# Power.net
KiCad netlist of a schematic drawn in Altium Designer
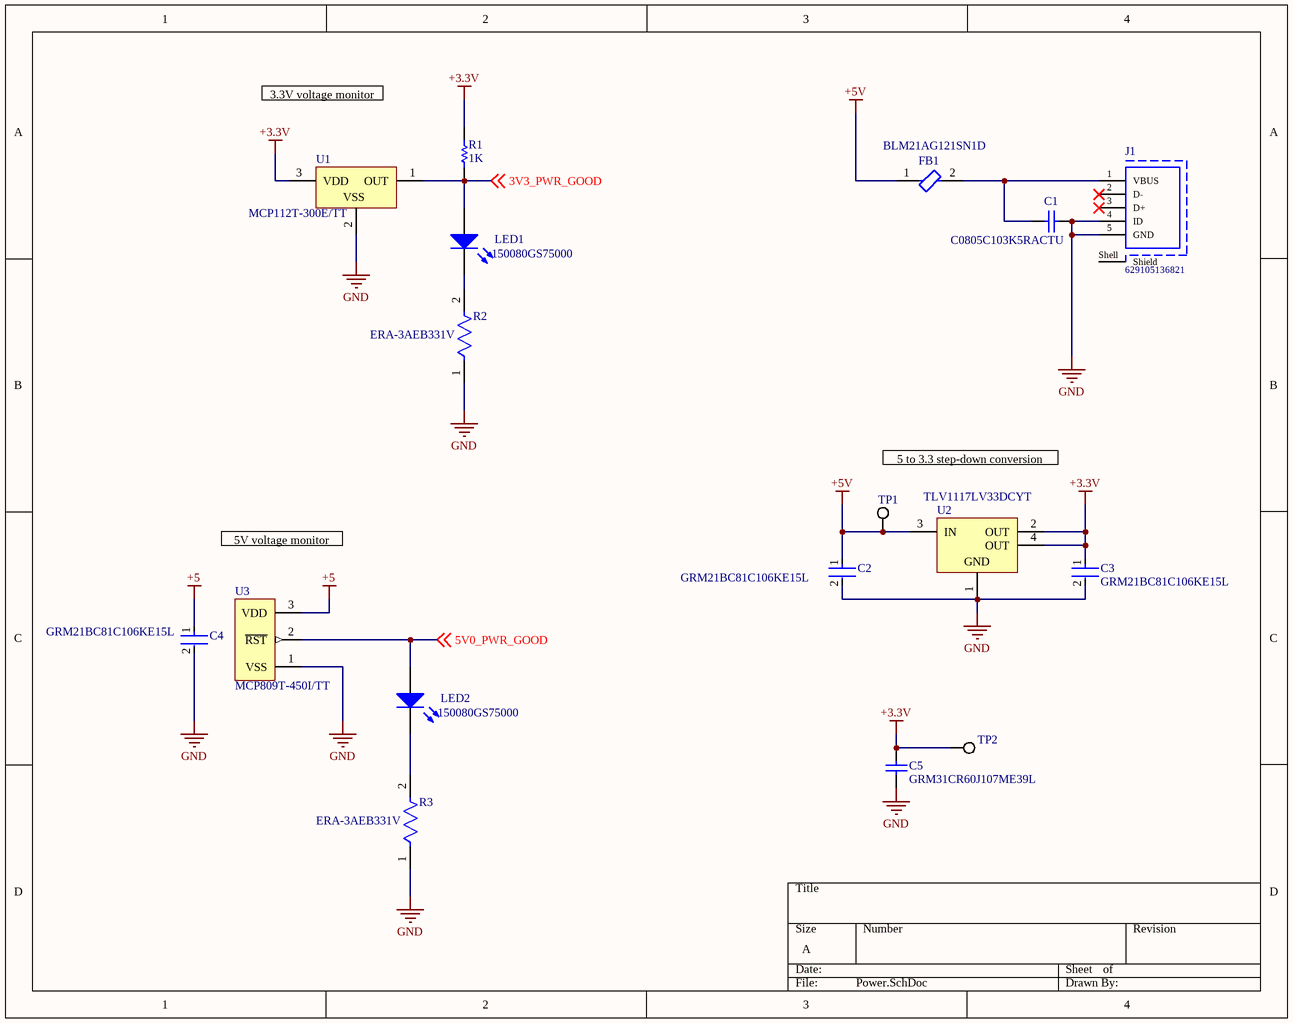
[diagram p0: Power.SchDoc]

(export (version "E")
  (design (tool "Eeschema 10.0.6"))
  (components
    (comp (ref "C1")
      (value "C0805C103K5RACTU")
      (footprint "CAPC2013X88X50LL20T25")
      (fields (field (name "MANUFACTURER") "Kemet"))
      (libsource (lib "Altium Content Vault") (part "CAP"))
    )
    (comp (ref "C2")
      (value "GRM21BC81C106KE15L")
      (footprint "FP-GRM21B-0_1-IPC_B")
      (description "Chip Multilayer Ceramic Capacitors for General Purpose, 0805, 10uF, X6S, 22%, 10%, 16V")
      (fields (field (name "VOLTAGE") "16V") (field (name "TOLERANCE") "10%"))
      (libsource (lib "Altium Content Vault") (part "b4654b650e69147ec39a6b967a45e02"))
    )
    (comp (ref "C3")
      (value "GRM21BC81C106KE15L")
      (footprint "FP-GRM21B-0_1-IPC_B")
      (description "Chip Multilayer Ceramic Capacitors for General Purpose, 0805, 10uF, X6S, 22%, 10%, 16V")
      (fields (field (name "VOLTAGE") "16V") (field (name "TOLERANCE") "10%"))
      (libsource (lib "Altium Content Vault") (part "b4654b650e69147ec39a6b967a45e02"))
    )
    (comp (ref "C4")
      (value "GRM21BC81C106KE15L")
      (footprint "FP-GRM21B-0_1-IPC_B")
      (description "Chip Multilayer Ceramic Capacitors for General Purpose, 0805, 10uF, X6S, 22%, 10%, 16V")
      (fields (field (name "VOLTAGE") "16V") (field (name "TOLERANCE") "10%"))
      (libsource (lib "Altium Content Vault") (part "b4654b650e69147ec39a6b967a45e02"))
    )
    (comp (ref "C5")
      (value "GRM31CR60J107ME39L")
      (footprint "CAPC3216X190X55ML30T25")
      (description "Chip Capacitor, 100 uF, +/- 20%, 6.3 V, -55 to 85 degC, 1206 (3216 Metric), RoHS, Tape and Reel")
      (fields (field (name "TOLERANCE") "20%"))
      (libsource (lib "Altium Content Vault") (part "CAP-NP-2"))
    )
    (comp (ref "FB1")
      (value "BLM21AG121SN1D")
      (footprint "FP-BLM21-0_2-t0_85-e0_5-IPC_A")
      (description "FERRITE BEAD 120 OHM 0805 1LN")
      (fields (field (name "TOLERANCE") "25%"))
      (libsource (lib "Altium Content Vault") (part "5f30dd21d616792df468990f7003faa"))
    )
    (comp (ref "J1")
      (value "629105136821")
      (footprint "629105136821")
      (description "Micro USB 2.0 Type B Receptacle WR-COM, Horizontal, SMT, with Pads and Pegs")
      (fields (field (name "MANUFACTURER") "Wurth Elektronik") (field (name "PUBLISHER") "WurthElektronik"))
      (libsource (lib "Altium Content Vault") (part "WE-USB-5-1SHLD"))
    )
    (comp (ref "LED1")
      (value "150080GS75000")
      (footprint "0805_A")
      (description "SMD mono-color Chip LED, WL-SMCW, Green")
      (fields (field (name "MANUFACTURER") "Wuerth Elektronik"))
      (libsource (lib "Altium Content Vault") (part "WE-LED_K1A2-2"))
    )
    (comp (ref "LED2")
      (value "150080GS75000")
      (footprint "0805_A")
      (description "SMD mono-color Chip LED, WL-SMCW, Green")
      (fields (field (name "MANUFACTURER") "Wuerth Elektronik"))
      (libsource (lib "Altium Content Vault") (part "WE-LED_K1A2-2"))
    )
    (comp (ref "R1")
      (value "1K")
      (description "Resistor")
      (libsource (lib "Simulation Generic Components") (part "Resistor"))
    )
    (comp (ref "R2")
      (value "ERA-3AEB331V")
      (footprint "FP-ERA3A-MFG")
      (description "RES SMD 330 OHM 0.1% 1/10W 0603")
      (fields (field (name "TOLERANCE") "0.1%"))
      (libsource (lib "Altium Content Vault") (part "8db39607336c341a927600551d01821"))
    )
    (comp (ref "R3")
      (value "ERA-3AEB331V")
      (footprint "FP-ERA3A-MFG")
      (description "RES SMD 330 OHM 0.1% 1/10W 0603")
      (fields (field (name "TOLERANCE") "0.1%"))
      (libsource (lib "Altium Content Vault") (part "8db39607336c341a927600551d01821"))
    )
    (comp (ref "TP1")
      (value "5019")
      (footprint "KSTN-5019_V")
      (description "Test Point, 1 Position SMD, RoHS, Tape and Reel")
      (libsource (lib "Altium Content Vault") (part "TESTPOINT_WHITE"))
    )
    (comp (ref "TP2")
      (value "5019")
      (footprint "KSTN-5019_V")
      (description "Test Point, 1 Position SMD, RoHS, Tape and Reel")
      (libsource (lib "Altium Content Vault") (part "TESTPOINT_WHITE"))
    )
    (comp (ref "U1")
      (value "MCP112T-300E/TT")
      (footprint "SOT-23-TT3_L")
      (libsource (lib "Altium Content Vault") (part "PM-VLTD-MCP11X-SOT3"))
    )
    (comp (ref "U2")
      (value "TLV1117LV33DCYT")
      (footprint "DCY0004A_M")
      (fields (field (name "MANUFACTURER") "Texas Instruments"))
      (libsource (lib "Altium Content Vault") (part "TI-TLV1117LV33DCY4"))
    )
    (comp (ref "U3")
      (value "MCP809T-450I/TT")
      (footprint "SOT-23-TT3_N")
      (libsource (lib "Altium Content Vault") (part "PM-SCCT-MCP809-3"))
    )
  )
  (nets
    (net (code "1") (name "+3.3V") (class "Default")
      (node (ref "C3") (pin "1") (pinfunction "1_1") (pintype "passive"))
      (node (ref "C5") (pin "2") (pinfunction "2_2") (pintype "passive"))
      (node (ref "R1") (pin "2") (pinfunction "2_2") (pintype "passive"))
      (node (ref "TP2") (pin "1") (pinfunction "1_1") (pintype "passive"))
      (node (ref "U1") (pin "3") (pinfunction "VDD_3") (pintype "power_in"))
      (node (ref "U2") (pin "2") (pinfunction "OUT_2") (pintype "power_in"))
      (node (ref "U2") (pin "4") (pinfunction "OUT_4") (pintype "power_in"))
    )
    (net (code "2") (name "+5") (class "Default")
      (node (ref "C4") (pin "1") (pinfunction "1_1") (pintype "passive"))
      (node (ref "U3") (pin "3") (pinfunction "VDD_3") (pintype "power_in"))
    )
    (net (code "3") (name "+5V") (class "Default")
      (node (ref "C2") (pin "1") (pinfunction "1_1") (pintype "passive"))
      (node (ref "FB1") (pin "1") (pinfunction "1_1") (pintype "passive"))
      (node (ref "TP1") (pin "1") (pinfunction "1_1") (pintype "passive"))
      (node (ref "U2") (pin "3") (pinfunction "IN_3") (pintype "power_in"))
    )
    (net (code "4") (name "3V3_PWR_GOOD") (class "Default")
      (node (ref "LED1") (pin "2") (pinfunction "A_2") (pintype "passive"))
      (node (ref "R1") (pin "1") (pinfunction "1_1") (pintype "passive"))
      (node (ref "U1") (pin "1") (pinfunction "OUT_1") (pintype "power_in"))
    )
    (net (code "5") (name "5V0_PWR_GOOD") (class "Default")
      (node (ref "LED2") (pin "2") (pinfunction "A_2") (pintype "passive"))
      (node (ref "U3") (pin "2") (pinfunction "~{RST}_2") (pintype "output"))
    )
    (net (code "6") (name "GND") (class "Default")
      (node (ref "C1") (pin "2") (pinfunction "2_2") (pintype "passive"))
      (node (ref "C2") (pin "2") (pinfunction "2_2") (pintype "passive"))
      (node (ref "C3") (pin "2") (pinfunction "2_2") (pintype "passive"))
      (node (ref "C4") (pin "2") (pinfunction "2_2") (pintype "passive"))
      (node (ref "C5") (pin "1") (pinfunction "1_1") (pintype "passive"))
      (node (ref "J1") (pin "4") (pinfunction "ID_4") (pintype "passive"))
      (node (ref "J1") (pin "5") (pinfunction "GND_5") (pintype "passive"))
      (node (ref "R2") (pin "1") (pinfunction "1_1") (pintype "passive"))
      (node (ref "R3") (pin "1") (pinfunction "1_1") (pintype "passive"))
      (node (ref "U1") (pin "2") (pinfunction "VSS_2") (pintype "power_in"))
      (node (ref "U2") (pin "1") (pinfunction "GND_1") (pintype "power_in"))
      (node (ref "U3") (pin "1") (pinfunction "VSS_1") (pintype "power_in"))
    )
    (net (code "7") (name "Net-(J1-VBUS)") (class "Default")
      (node (ref "C1") (pin "1") (pinfunction "1_1") (pintype "passive"))
      (node (ref "FB1") (pin "2") (pinfunction "2_2") (pintype "passive"))
      (node (ref "J1") (pin "1") (pinfunction "VBUS_1") (pintype "passive"))
    )
    (net (code "8") (name "Net-(LED1-K)") (class "Default")
      (node (ref "LED1") (pin "1") (pinfunction "K_1") (pintype "passive"))
      (node (ref "R2") (pin "2") (pinfunction "2_2") (pintype "passive"))
    )
    (net (code "9") (name "Net-(LED2-K)") (class "Default")
      (node (ref "LED2") (pin "1") (pinfunction "K_1") (pintype "passive"))
      (node (ref "R3") (pin "2") (pinfunction "2_2") (pintype "passive"))
    )
    (net (code "10") (name "unconnected-(J1-D+-Pad3)") (class "Default")
      (node (ref "J1") (pin "3") (pinfunction "D+_3") (pintype "passive+no_connect"))
    )
    (net (code "11") (name "unconnected-(J1-D--Pad2)") (class "Default")
      (node (ref "J1") (pin "2") (pinfunction "D-_2") (pintype "passive+no_connect"))
    )
    (net (code "12") (name "unconnected-(J1-Shield-PadShell)") (class "Default")
      (node (ref "J1") (pin "Shell") (pinfunction "Shield_Shell") (pintype "passive"))
    )
  )
)
